# POWER_SUPPLY.net
KiCad netlist of a schematic drawn in Altium Designer
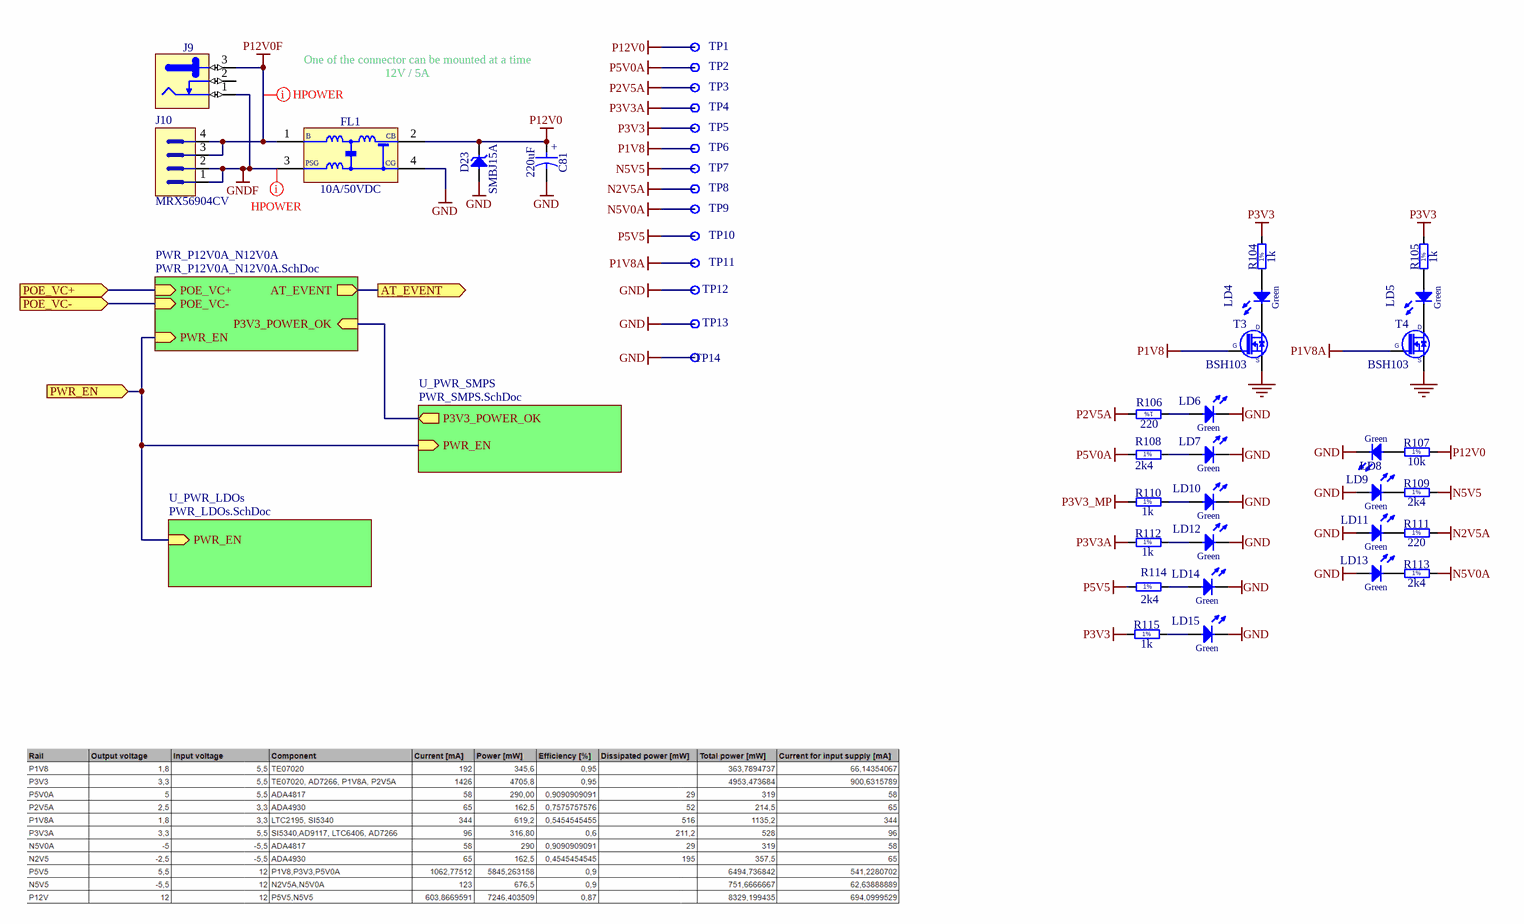
[diagram p0: POWER_SUPPLY.SchDoc]

(export (version "E")
  (design (tool "Eeschema 10.0.6"))
  (components
    (comp (ref "C81")
      (value "220uF")
      (footprint "CAPAE830X620N")
      (description "Polarised capacitor")
      (fields
        (field (name "PART NUMBER") "CAE830-620_220UF_16V_20%")
        (field (name "VOLTAGE") "16V")
        (field (name "AUTHOR") "CERN DEM JLC")
      )
      (libsource (lib "Capacitors") (part "Capacitor - polarized"))
    )
    (comp (ref "D23")
      (value "SMBJ15A")
      (footprint "DIOM5336X265N")
      (description "Zener Diode")
      (fields
        (field (name "VOLTAGE") "15V")
        (field (name "POWER") "600W")
        (field (name "AUTHOR") "CERN DEM JLC")
      )
      (libsource (lib "ICs And Semiconductors") (part "Diode Zener"))
    )
    (comp (ref "FL1")
      (value "10A/50VDC")
      (footprint "FIL_MURATA_BNX02")
      (description "Block Type EMIFIL (LC Combined)")
      (fields
        (field (name "PART NUMBER") "FIL_MURATA_BNX022-01L")
        (field (name "MANUFACTURER") "MURATA")
        (field (name "AUTHOR") "CERN DEM JLC")
      )
      (libsource (lib "Inductors & Transformers") (part "FIL_MURATA_BNX02"))
    )
    (comp (ref "J9")
      (value "Jack")
      (footprint "SWITCHCRAFT_L712RA")
      (description "24V /3. 5A, 2.1mm Diameter Pin, SMD DC Power Supply Connector With  Break Contact")
      (fields
        (field (name "PART NUMBER") "SWITCHCRAFT_L712RA")
        (field (name "MANUFACTURER") "SWITCHCRAFT")
        (field (name "AUTHOR") "GK")
      )
      (libsource (lib "Stabilizer") (part "CON_DC_5A_THT_RA"))
    )
    (comp (ref "J10")
      (value "MRX56904CV")
      (footprint "MRX56904CV")
      (description "4.2mm cripm terminal header")
      (libsource (lib "Stabilizer") (part "CON_CRIMP_4.2mm_RA_4"))
    )
    (comp (ref "LD4")
      (value "Green")
      (footprint "LED_KINGBRIGHT_KPH-1608CGCK")
      (description "LED Green 1C 2A")
      (fields
        (field (name "MANUFACTURER PART NUMBER") "KPH-1608CGCK")
        (field (name "PART NUMBER") "LED_KINGBRIGHT_KPH-1608CGCK")
        (field (name "AUTHOR") "CERN DEM JLC")
      )
      (libsource (lib "ICs And Semiconductors") (part "LED Green 1C 2A"))
    )
    (comp (ref "LD5")
      (value "Green")
      (footprint "LED_KINGBRIGHT_KPH-1608CGCK")
      (description "LED Green 1C 2A")
      (fields
        (field (name "MANUFACTURER PART NUMBER") "KPH-1608CGCK")
        (field (name "PART NUMBER") "LED_KINGBRIGHT_KPH-1608CGCK")
        (field (name "AUTHOR") "CERN DEM JLC")
      )
      (libsource (lib "ICs And Semiconductors") (part "LED Green 1C 2A"))
    )
    (comp (ref "LD6")
      (value "Green")
      (footprint "LED_KINGBRIGHT_KPH-1608CGCK")
      (description "LED Green 1C 2A")
      (fields
        (field (name "PART NUMBER") "LED_KINGBRIGHT_KPH-1608CGCK")
        (field (name "MANUFACTURER") "KINGBRIGHT")
        (field (name "AUTHOR") "CERN DEM JLC")
      )
      (libsource (lib "ICs And Semiconductors") (part "LED Green 1C 2A"))
    )
    (comp (ref "LD7")
      (value "Green")
      (footprint "LED_KINGBRIGHT_KPH-1608CGCK")
      (description "LED Green 1C 2A")
      (fields
        (field (name "PART NUMBER") "LED_KINGBRIGHT_KPH-1608CGCK")
        (field (name "MANUFACTURER") "KINGBRIGHT")
        (field (name "AUTHOR") "CERN DEM JLC")
      )
      (libsource (lib "ICs And Semiconductors") (part "LED Green 1C 2A"))
    )
    (comp (ref "LD8")
      (value "Green")
      (footprint "LED_KINGBRIGHT_KPH-1608CGCK")
      (description "LED Green 1C 2A")
      (fields
        (field (name "PART NUMBER") "LED_KINGBRIGHT_KPH-1608CGCK")
        (field (name "MANUFACTURER") "KINGBRIGHT")
        (field (name "AUTHOR") "CERN DEM JLC")
      )
      (libsource (lib "ICs And Semiconductors") (part "LED Green 1C 2A"))
    )
    (comp (ref "LD9")
      (value "Green")
      (footprint "LED_KINGBRIGHT_KPH-1608CGCK")
      (description "LED Green 1C 2A")
      (fields
        (field (name "PART NUMBER") "LED_KINGBRIGHT_KPH-1608CGCK")
        (field (name "MANUFACTURER") "KINGBRIGHT")
        (field (name "AUTHOR") "CERN DEM JLC")
      )
      (libsource (lib "ICs And Semiconductors") (part "LED Green 1C 2A"))
    )
    (comp (ref "LD10")
      (value "Green")
      (footprint "LED_KINGBRIGHT_KPH-1608CGCK")
      (description "LED Green 1C 2A")
      (fields
        (field (name "PART NUMBER") "LED_KINGBRIGHT_KPH-1608CGCK")
        (field (name "MANUFACTURER") "KINGBRIGHT")
        (field (name "AUTHOR") "CERN DEM JLC")
      )
      (libsource (lib "ICs And Semiconductors") (part "LED Green 1C 2A"))
    )
    (comp (ref "LD11")
      (value "Green")
      (footprint "LED_KINGBRIGHT_KPH-1608CGCK")
      (description "LED Green 1C 2A")
      (fields
        (field (name "PART NUMBER") "LED_KINGBRIGHT_KPH-1608CGCK")
        (field (name "MANUFACTURER") "KINGBRIGHT")
        (field (name "AUTHOR") "CERN DEM JLC")
      )
      (libsource (lib "ICs And Semiconductors") (part "LED Green 1C 2A"))
    )
    (comp (ref "LD12")
      (value "Green")
      (footprint "LED_KINGBRIGHT_KPH-1608CGCK")
      (description "LED Green 1C 2A")
      (fields
        (field (name "PART NUMBER") "LED_KINGBRIGHT_KPH-1608CGCK")
        (field (name "MANUFACTURER") "KINGBRIGHT")
        (field (name "AUTHOR") "CERN DEM JLC")
      )
      (libsource (lib "ICs And Semiconductors") (part "LED Green 1C 2A"))
    )
    (comp (ref "LD13")
      (value "Green")
      (footprint "LED_KINGBRIGHT_KPH-1608CGCK")
      (description "LED Green 1C 2A")
      (fields
        (field (name "PART NUMBER") "LED_KINGBRIGHT_KPH-1608CGCK")
        (field (name "MANUFACTURER") "KINGBRIGHT")
        (field (name "AUTHOR") "CERN DEM JLC")
      )
      (libsource (lib "ICs And Semiconductors") (part "LED Green 1C 2A"))
    )
    (comp (ref "LD14")
      (value "Green")
      (footprint "LED_KINGBRIGHT_KPH-1608CGCK")
      (description "LED Green 1C 2A")
      (fields
        (field (name "PART NUMBER") "LED_KINGBRIGHT_KPH-1608CGCK")
        (field (name "MANUFACTURER") "KINGBRIGHT")
        (field (name "AUTHOR") "CERN DEM JLC")
      )
      (libsource (lib "ICs And Semiconductors") (part "LED Green 1C 2A"))
    )
    (comp (ref "LD15")
      (value "Green")
      (footprint "LED_KINGBRIGHT_KPH-1608CGCK")
      (description "LED Green 1C 2A")
      (fields
        (field (name "PART NUMBER") "LED_KINGBRIGHT_KPH-1608CGCK")
        (field (name "MANUFACTURER") "KINGBRIGHT")
        (field (name "AUTHOR") "CERN DEM JLC")
      )
      (libsource (lib "ICs And Semiconductors") (part "LED Green 1C 2A"))
    )
    (comp (ref "R104")
      (value "1k")
      (footprint "RESC1005X40N")
      (description "Resistor - 1%")
      (fields
        (field (name "PART NUMBER") "R0402_1K_1%_0.0625W_100PPM")
        (field (name "POWER") "0.0625W")
        (field (name "AUTHOR") "CERN DEM JLC")
      )
      (libsource (lib "Resistors") (part "Resistor - 1%"))
    )
    (comp (ref "R105")
      (value "1k")
      (footprint "RESC1005X40N")
      (description "Resistor - 1%")
      (fields
        (field (name "PART NUMBER") "R0402_1K_1%_0.0625W_100PPM")
        (field (name "POWER") "0.0625W")
        (field (name "AUTHOR") "CERN DEM JLC")
      )
      (libsource (lib "Resistors") (part "Resistor - 1%"))
    )
    (comp (ref "R106")
      (value "220")
      (footprint "RESC1608X55N")
      (description "Resistor - 1%")
      (fields
        (field (name "PART NUMBER") "R0603_220R_1%_0.1W_100PPM")
        (field (name "POWER") "0.1W")
        (field (name "AUTHOR") "CERN DEM JLC")
      )
      (libsource (lib "Resistors") (part "Resistor - 1%"))
    )
    (comp (ref "R107")
      (value "10k")
      (footprint "RESC1005X40N")
      (description "Resistor - 1%")
      (fields
        (field (name "PART NUMBER") "R0402_10K_1%_0.0625W_100PPM")
        (field (name "POWER") "0.0625W")
        (field (name "AUTHOR") "CERN DEM JLC")
      )
      (libsource (lib "Resistors") (part "Resistor - 1%"))
    )
    (comp (ref "R108")
      (value "2k4")
      (footprint "RESC1005X40N")
      (description "Resistor - 1%")
      (fields
        (field (name "PART NUMBER") "R0402_2K4_1%_0.0625W_100PPM")
        (field (name "POWER") "0.0625W")
        (field (name "AUTHOR") "CERN DEM JLC")
      )
      (libsource (lib "Resistors") (part "Resistor - 1%"))
    )
    (comp (ref "R109")
      (value "2k4")
      (footprint "RESC1005X40N")
      (description "Resistor - 1%")
      (fields
        (field (name "PART NUMBER") "R0402_2K4_1%_0.0625W_100PPM")
        (field (name "POWER") "0.0625W")
        (field (name "AUTHOR") "CERN DEM JLC")
      )
      (libsource (lib "Resistors") (part "Resistor - 1%"))
    )
    (comp (ref "R110")
      (value "1k")
      (footprint "RESC1005X40N")
      (description "Resistor - 1%")
      (fields
        (field (name "PART NUMBER") "R0402_1K_1%_0.0625W_100PPM")
        (field (name "POWER") "0.0625W")
        (field (name "AUTHOR") "CERN DEM JLC")
      )
      (libsource (lib "Resistors") (part "Resistor - 1%"))
    )
    (comp (ref "R111")
      (value "220")
      (footprint "RESC1608X55N")
      (description "Resistor - 1%")
      (fields
        (field (name "PART NUMBER") "R0603_220R_1%_0.1W_100PPM")
        (field (name "POWER") "0.1W")
        (field (name "AUTHOR") "CERN DEM JLC")
      )
      (libsource (lib "Resistors") (part "Resistor - 1%"))
    )
    (comp (ref "R112")
      (value "1k")
      (footprint "RESC1005X40N")
      (description "Resistor - 1%")
      (fields
        (field (name "PART NUMBER") "R0402_1K_1%_0.0625W_100PPM")
        (field (name "POWER") "0.0625W")
        (field (name "AUTHOR") "CERN DEM JLC")
      )
      (libsource (lib "Resistors") (part "Resistor - 1%"))
    )
    (comp (ref "R113")
      (value "2k4")
      (footprint "RESC1005X40N")
      (description "Resistor - 1%")
      (fields
        (field (name "PART NUMBER") "R0402_2K4_1%_0.0625W_100PPM")
        (field (name "POWER") "0.0625W")
        (field (name "AUTHOR") "CERN DEM JLC")
      )
      (libsource (lib "Resistors") (part "Resistor - 1%"))
    )
    (comp (ref "R114")
      (value "2k4")
      (footprint "RESC1005X40N")
      (description "Resistor - 1%")
      (fields
        (field (name "PART NUMBER") "R0402_2K4_1%_0.0625W_100PPM")
        (field (name "POWER") "0.0625W")
        (field (name "AUTHOR") "CERN DEM JLC")
      )
      (libsource (lib "Resistors") (part "Resistor - 1%"))
    )
    (comp (ref "R115")
      (value "1k")
      (footprint "RESC1005X40N")
      (description "Resistor - 1%")
      (fields
        (field (name "PART NUMBER") "R0402_1K_1%_0.0625W_100PPM")
        (field (name "POWER") "0.0625W")
        (field (name "AUTHOR") "CERN DEM JLC")
      )
      (libsource (lib "Resistors") (part "Resistor - 1%"))
    )
    (comp (ref "T3")
      (value "BSH103")
      (footprint "SOT95P230X110-3N")
      (description "N-CHANNEL MOSFET WITH DIODE")
      (fields (field (name "MANUFACTURER") "NEXPERIA") (field (name "AUTHOR") "CERN DEM JLC"))
      (libsource (lib "ICs And Semiconductors") (part "N-MOSFET-D 1G 2S 3D"))
    )
    (comp (ref "T4")
      (value "BSH103")
      (footprint "SOT95P230X110-3N")
      (description "N-CHANNEL MOSFET WITH DIODE")
      (fields (field (name "MANUFACTURER") "NEXPERIA") (field (name "AUTHOR") "CERN DEM JLC"))
      (libsource (lib "ICs And Semiconductors") (part "N-MOSFET-D 1G 2S 3D"))
    )
    (comp (ref "TP1")
      (value "Test Point")
      (footprint "TPS127")
      (fields (field (name "PART NUMBER") "SMD_PAD_1.27X1.27MM") (field (name "AUTHOR") "CERN DEM JLC"))
      (libsource (lib "Eletro-mechanical") (part "Test Point"))
    )
    (comp (ref "TP2")
      (value "Test Point")
      (footprint "TPS127")
      (fields (field (name "PART NUMBER") "SMD_PAD_1.27X1.27MM") (field (name "AUTHOR") "CERN DEM JLC"))
      (libsource (lib "Eletro-mechanical") (part "Test Point"))
    )
    (comp (ref "TP3")
      (value "Test Point")
      (footprint "TPS127")
      (fields (field (name "PART NUMBER") "SMD_PAD_1.27X1.27MM") (field (name "AUTHOR") "CERN DEM JLC"))
      (libsource (lib "Eletro-mechanical") (part "Test Point"))
    )
    (comp (ref "TP4")
      (value "Test Point")
      (footprint "TPS127")
      (fields (field (name "PART NUMBER") "SMD_PAD_1.27X1.27MM") (field (name "AUTHOR") "CERN DEM JLC"))
      (libsource (lib "Eletro-mechanical") (part "Test Point"))
    )
    (comp (ref "TP5")
      (value "Test Point")
      (footprint "TPS127")
      (fields (field (name "PART NUMBER") "SMD_PAD_1.27X1.27MM") (field (name "AUTHOR") "CERN DEM JLC"))
      (libsource (lib "Eletro-mechanical") (part "Test Point"))
    )
    (comp (ref "TP6")
      (value "Test Point")
      (footprint "TPS127")
      (fields (field (name "PART NUMBER") "SMD_PAD_1.27X1.27MM") (field (name "AUTHOR") "CERN DEM JLC"))
      (libsource (lib "Eletro-mechanical") (part "Test Point"))
    )
    (comp (ref "TP7")
      (value "Test Point")
      (footprint "TPS127")
      (fields (field (name "PART NUMBER") "SMD_PAD_1.27X1.27MM") (field (name "AUTHOR") "CERN DEM JLC"))
      (libsource (lib "Eletro-mechanical") (part "Test Point"))
    )
    (comp (ref "TP8")
      (value "Test Point")
      (footprint "TPS127")
      (fields (field (name "PART NUMBER") "SMD_PAD_1.27X1.27MM") (field (name "AUTHOR") "CERN DEM JLC"))
      (libsource (lib "Eletro-mechanical") (part "Test Point"))
    )
    (comp (ref "TP9")
      (value "Test Point")
      (footprint "TPS127")
      (fields (field (name "PART NUMBER") "SMD_PAD_1.27X1.27MM") (field (name "AUTHOR") "CERN DEM JLC"))
      (libsource (lib "Eletro-mechanical") (part "Test Point"))
    )
    (comp (ref "TP10")
      (value "Test Point")
      (footprint "TPS127")
      (fields (field (name "PART NUMBER") "SMD_PAD_1.27X1.27MM") (field (name "AUTHOR") "CERN DEM JLC"))
      (libsource (lib "Eletro-mechanical") (part "Test Point"))
    )
    (comp (ref "TP11")
      (value "Test Point")
      (footprint "TPS127")
      (fields (field (name "PART NUMBER") "SMD_PAD_1.27X1.27MM") (field (name "AUTHOR") "CERN DEM JLC"))
      (libsource (lib "Eletro-mechanical") (part "Test Point"))
    )
    (comp (ref "TP12")
      (value "Test Point")
      (footprint "TPS127")
      (fields (field (name "PART NUMBER") "SMD_PAD_1.27X1.27MM") (field (name "AUTHOR") "CERN DEM JLC"))
      (libsource (lib "Eletro-mechanical") (part "Test Point"))
    )
    (comp (ref "TP13")
      (value "Test Point")
      (footprint "TPS127")
      (fields (field (name "PART NUMBER") "SMD_PAD_1.27X1.27MM") (field (name "AUTHOR") "CERN DEM JLC"))
      (libsource (lib "Eletro-mechanical") (part "Test Point"))
    )
    (comp (ref "TP14")
      (value "Plated Hole")
      (footprint "c150h100")
      (description "Single Terminal Socket")
      (fields (field (name "PART NUMBER") "PLATED_HOLE1.0_PAD1.5") (field (name "AUTHOR") "CERN DEM JLC"))
      (libsource (lib "Eletro-mechanical") (part "Single Terminal Socket"))
    )
  )
  (nets
    (net (code "6") (name "GND") (class "Default")
      (node (ref "C81") (pin "2") (pinfunction "2_2") (pintype "passive"))
      (node (ref "D23") (pin "2") (pinfunction "A_2") (pintype "passive"))
      (node (ref "FL1") (pin "4") (pinfunction "CG_4") (pintype "passive"))
      (node (ref "LD10") (pin "1") (pinfunction "C_1") (pintype "passive"))
      (node (ref "LD11") (pin "2") (pinfunction "A_2") (pintype "passive"))
      (node (ref "LD12") (pin "1") (pinfunction "C_1") (pintype "passive"))
      (node (ref "LD13") (pin "2") (pinfunction "A_2") (pintype "passive"))
      (node (ref "LD14") (pin "1") (pinfunction "C_1") (pintype "passive"))
      (node (ref "LD15") (pin "1") (pinfunction "C_1") (pintype "passive"))
      (node (ref "LD6") (pin "1") (pinfunction "C_1") (pintype "passive"))
      (node (ref "LD7") (pin "1") (pinfunction "C_1") (pintype "passive"))
      (node (ref "LD8") (pin "1") (pinfunction "C_1") (pintype "passive"))
      (node (ref "LD9") (pin "2") (pinfunction "A_2") (pintype "passive"))
      (node (ref "T3") (pin "2") (pinfunction "S_2") (pintype "passive"))
      (node (ref "T4") (pin "2") (pinfunction "S_2") (pintype "passive"))
      (node (ref "TP12") (pin "1") (pinfunction "1_1") (pintype "bidirectional"))
      (node (ref "TP13") (pin "1") (pinfunction "1_1") (pintype "bidirectional"))
      (node (ref "TP14") (pin "1") (pinfunction "1_1") (pintype "bidirectional"))
    )
    (net (code "7") (name "GNDF") (class "Default")
      (node (ref "FL1") (pin "3") (pinfunction "PSG_3") (pintype "passive"))
      (node (ref "J10") (pin "1") (pinfunction "1_1") (pintype "bidirectional"))
      (node (ref "J10") (pin "2") (pinfunction "2_2") (pintype "bidirectional"))
      (node (ref "J9") (pin "1") (pinfunction "1_1") (pintype "bidirectional"))
    )
    (net (code "8") (name "N2V5A") (class "Default")
      (node (ref "R111") (pin "2") (pinfunction "2_2") (pintype "passive"))
      (node (ref "TP8") (pin "1") (pinfunction "1_1") (pintype "bidirectional"))
    )
    (net (code "9") (name "N5V0A") (class "Default")
      (node (ref "R113") (pin "2") (pinfunction "2_2") (pintype "passive"))
      (node (ref "TP9") (pin "1") (pinfunction "1_1") (pintype "bidirectional"))
    )
    (net (code "10") (name "N5V5") (class "Default")
      (node (ref "R109") (pin "2") (pinfunction "2_2") (pintype "passive"))
      (node (ref "TP7") (pin "1") (pinfunction "1_1") (pintype "bidirectional"))
    )
    (net (code "11") (name "Net-(LD4-A)") (class "Default")
      (node (ref "LD4") (pin "2") (pinfunction "A_2") (pintype "passive"))
      (node (ref "R104") (pin "1") (pinfunction "1_1") (pintype "passive"))
    )
    (net (code "12") (name "Net-(LD4-C)") (class "Default")
      (node (ref "LD4") (pin "1") (pinfunction "C_1") (pintype "passive"))
      (node (ref "T3") (pin "3") (pinfunction "D_3") (pintype "passive"))
    )
    (net (code "13") (name "Net-(LD5-A)") (class "Default")
      (node (ref "LD5") (pin "2") (pinfunction "A_2") (pintype "passive"))
      (node (ref "R105") (pin "1") (pinfunction "1_1") (pintype "passive"))
    )
    (net (code "14") (name "Net-(LD5-C)") (class "Default")
      (node (ref "LD5") (pin "1") (pinfunction "C_1") (pintype "passive"))
      (node (ref "T4") (pin "3") (pinfunction "D_3") (pintype "passive"))
    )
    (net (code "15") (name "Net-(LD6-A)") (class "Default")
      (node (ref "LD6") (pin "2") (pinfunction "A_2") (pintype "passive"))
      (node (ref "R106") (pin "1") (pinfunction "1_1") (pintype "passive"))
    )
    (net (code "16") (name "Net-(LD7-A)") (class "Default")
      (node (ref "LD7") (pin "2") (pinfunction "A_2") (pintype "passive"))
      (node (ref "R108") (pin "2") (pinfunction "2_2") (pintype "passive"))
    )
    (net (code "17") (name "Net-(LD8-A)") (class "Default")
      (node (ref "LD8") (pin "2") (pinfunction "A_2") (pintype "passive"))
      (node (ref "R107") (pin "1") (pinfunction "1_1") (pintype "passive"))
    )
    (net (code "18") (name "Net-(LD9-C)") (class "Default")
      (node (ref "LD9") (pin "1") (pinfunction "C_1") (pintype "passive"))
      (node (ref "R109") (pin "1") (pinfunction "1_1") (pintype "passive"))
    )
    (net (code "19") (name "Net-(LD10-A)") (class "Default")
      (node (ref "LD10") (pin "2") (pinfunction "A_2") (pintype "passive"))
      (node (ref "R110") (pin "2") (pinfunction "2_2") (pintype "passive"))
    )
    (net (code "20") (name "Net-(LD11-C)") (class "Default")
      (node (ref "LD11") (pin "1") (pinfunction "C_1") (pintype "passive"))
      (node (ref "R111") (pin "1") (pinfunction "1_1") (pintype "passive"))
    )
    (net (code "21") (name "Net-(LD12-A)") (class "Default")
      (node (ref "LD12") (pin "2") (pinfunction "A_2") (pintype "passive"))
      (node (ref "R112") (pin "2") (pinfunction "2_2") (pintype "passive"))
    )
    (net (code "22") (name "Net-(LD13-C)") (class "Default")
      (node (ref "LD13") (pin "1") (pinfunction "C_1") (pintype "passive"))
      (node (ref "R113") (pin "1") (pinfunction "1_1") (pintype "passive"))
    )
    (net (code "23") (name "Net-(LD14-A)") (class "Default")
      (node (ref "LD14") (pin "2") (pinfunction "A_2") (pintype "passive"))
      (node (ref "R114") (pin "2") (pinfunction "2_2") (pintype "passive"))
    )
    (net (code "24") (name "Net-(LD15-A)") (class "Default")
      (node (ref "LD15") (pin "2") (pinfunction "A_2") (pintype "passive"))
      (node (ref "R115") (pin "2") (pinfunction "2_2") (pintype "passive"))
    )
    (net (code "25") (name "P1V8") (class "Default")
      (node (ref "T3") (pin "1") (pinfunction "G_1") (pintype "passive"))
      (node (ref "TP6") (pin "1") (pinfunction "1_1") (pintype "bidirectional"))
    )
    (net (code "26") (name "P1V8A") (class "Default")
      (node (ref "T4") (pin "1") (pinfunction "G_1") (pintype "passive"))
      (node (ref "TP11") (pin "1") (pinfunction "1_1") (pintype "bidirectional"))
    )
    (net (code "27") (name "P2V5A") (class "Default")
      (node (ref "R106") (pin "2") (pinfunction "2_2") (pintype "passive"))
      (node (ref "TP3") (pin "1") (pinfunction "1_1") (pintype "bidirectional"))
    )
    (net (code "28") (name "P3V3") (class "Default")
      (node (ref "R104") (pin "2") (pinfunction "2_2") (pintype "passive"))
      (node (ref "R105") (pin "2") (pinfunction "2_2") (pintype "passive"))
      (node (ref "R115") (pin "1") (pinfunction "1_1") (pintype "passive"))
      (node (ref "TP5") (pin "1") (pinfunction "1_1") (pintype "bidirectional"))
    )
    (net (code "29") (name "P3V3A") (class "Default")
      (node (ref "R112") (pin "1") (pinfunction "1_1") (pintype "passive"))
      (node (ref "TP4") (pin "1") (pinfunction "1_1") (pintype "bidirectional"))
    )
    (net (code "30") (name "P3V3_MP") (class "Default")
      (node (ref "R110") (pin "1") (pinfunction "1_1") (pintype "passive"))
    )
    (net (code "31") (name "P5V0A") (class "Default")
      (node (ref "R108") (pin "1") (pinfunction "1_1") (pintype "passive"))
      (node (ref "TP2") (pin "1") (pinfunction "1_1") (pintype "bidirectional"))
    )
    (net (code "32") (name "P5V5") (class "Default")
      (node (ref "R114") (pin "1") (pinfunction "1_1") (pintype "passive"))
      (node (ref "TP10") (pin "1") (pinfunction "1_1") (pintype "bidirectional"))
    )
    (net (code "33") (name "P12V0") (class "Default")
      (node (ref "C81") (pin "1") (pinfunction "1_1") (pintype "passive"))
      (node (ref "D23") (pin "1") (pinfunction "C_1") (pintype "passive"))
      (node (ref "FL1") (pin "2") (pinfunction "CB_2") (pintype "passive"))
      (node (ref "R107") (pin "2") (pinfunction "2_2") (pintype "passive"))
      (node (ref "TP1") (pin "1") (pinfunction "1_1") (pintype "bidirectional"))
    )
    (net (code "34") (name "P12V0F") (class "Default")
      (node (ref "FL1") (pin "1") (pinfunction "B_1") (pintype "passive"))
      (node (ref "J10") (pin "3") (pinfunction "3_3") (pintype "bidirectional"))
      (node (ref "J10") (pin "4") (pinfunction "4_4") (pintype "bidirectional"))
      (node (ref "J9") (pin "3") (pinfunction "3_3") (pintype "bidirectional"))
    )
    (net (code "35") (name "unconnected-(J9-Pad2)") (class "Default")
      (node (ref "J9") (pin "2") (pinfunction "2_2") (pintype "bidirectional"))
    )
  )
)
